# PWR.net
KiCad netlist of a schematic drawn in Altium Designer
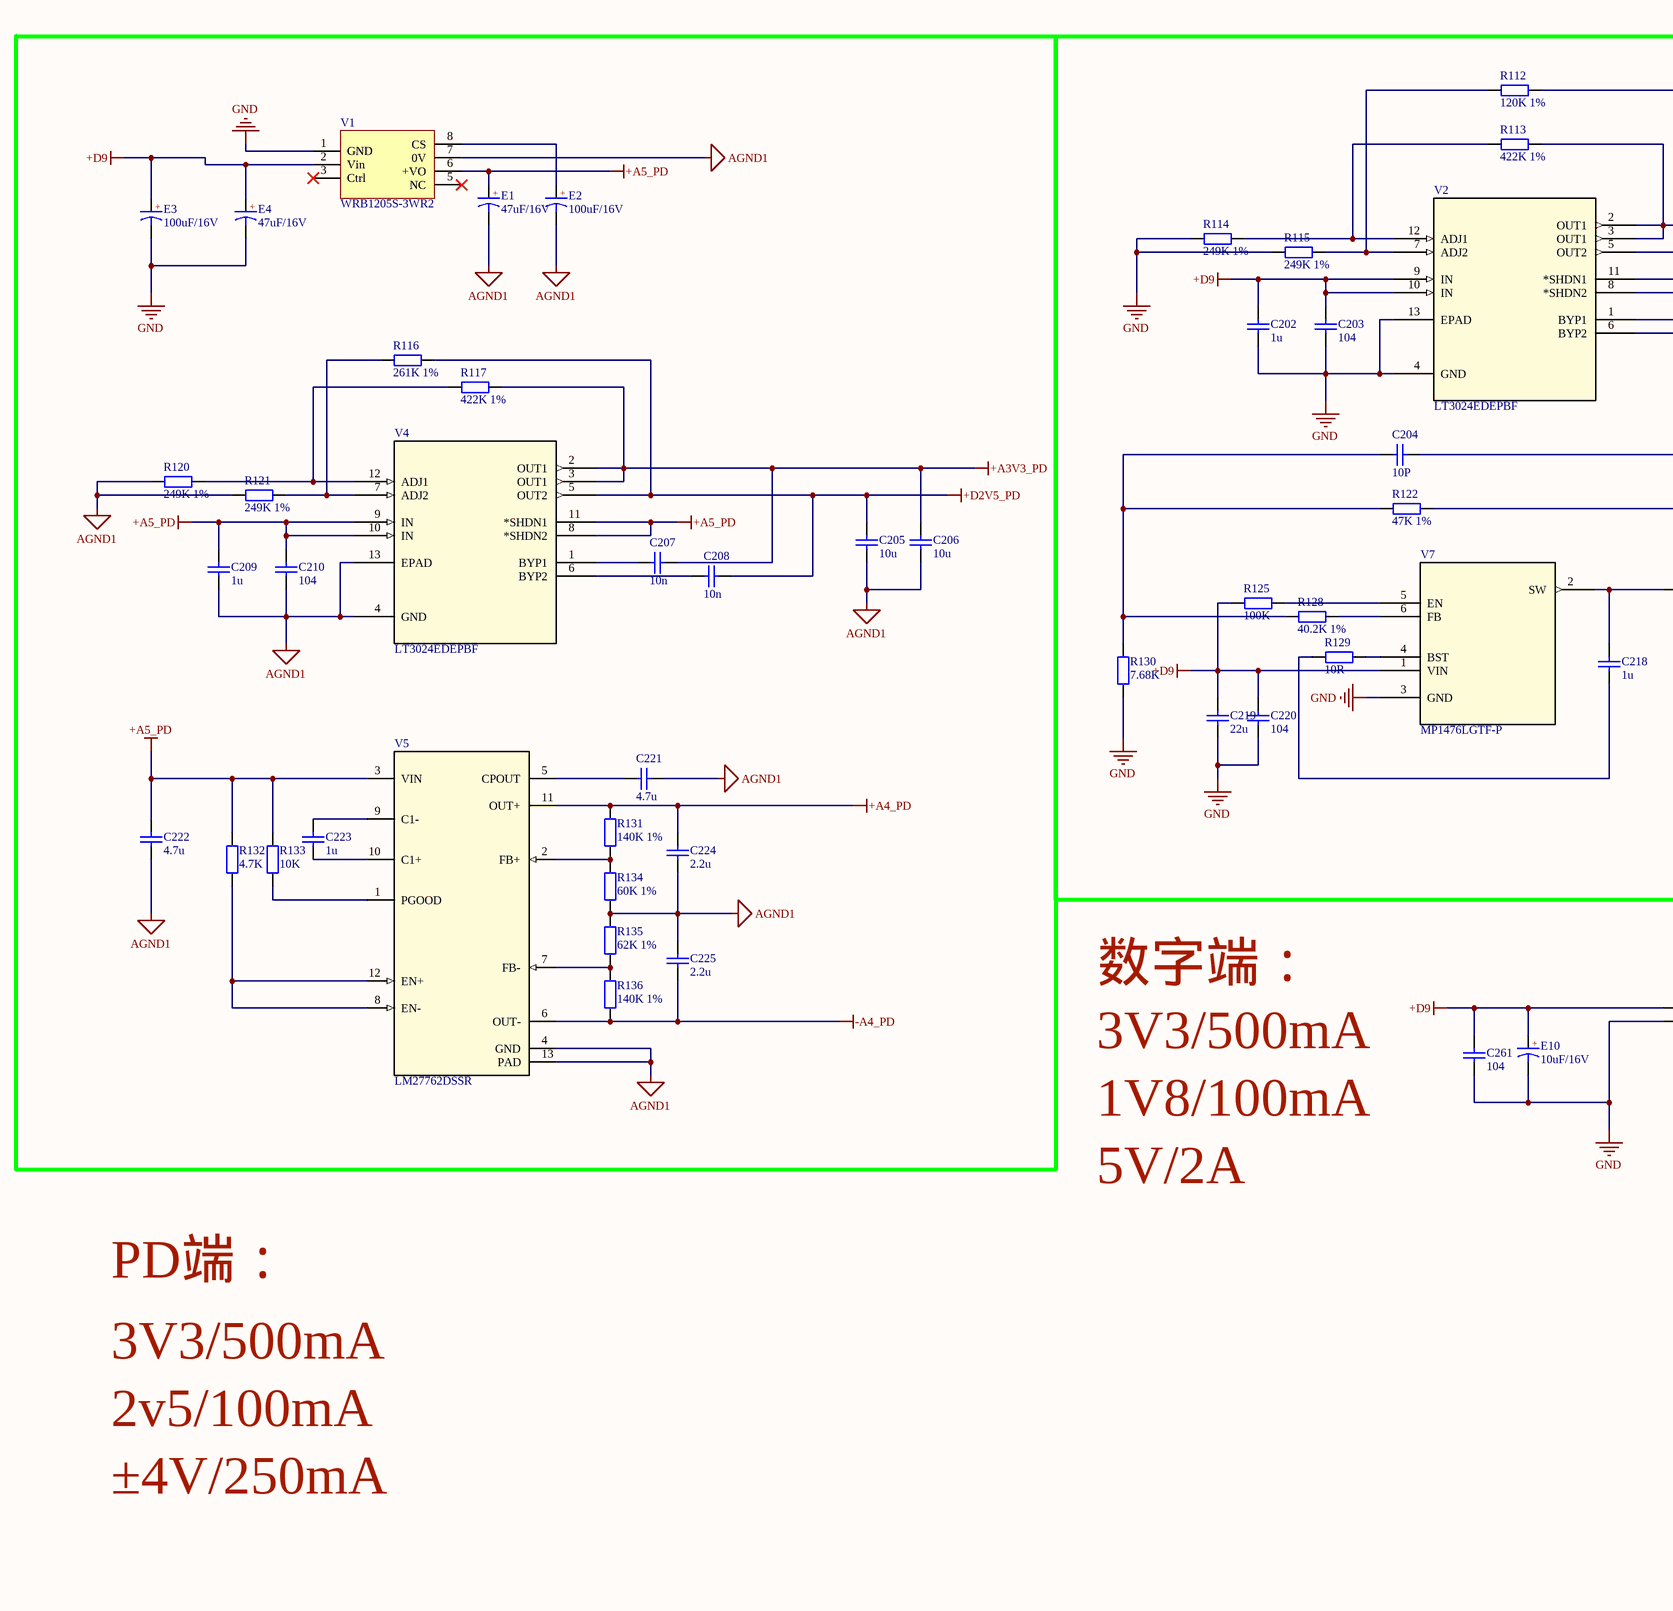
[diagram p0: PWR.SchDoc, left]
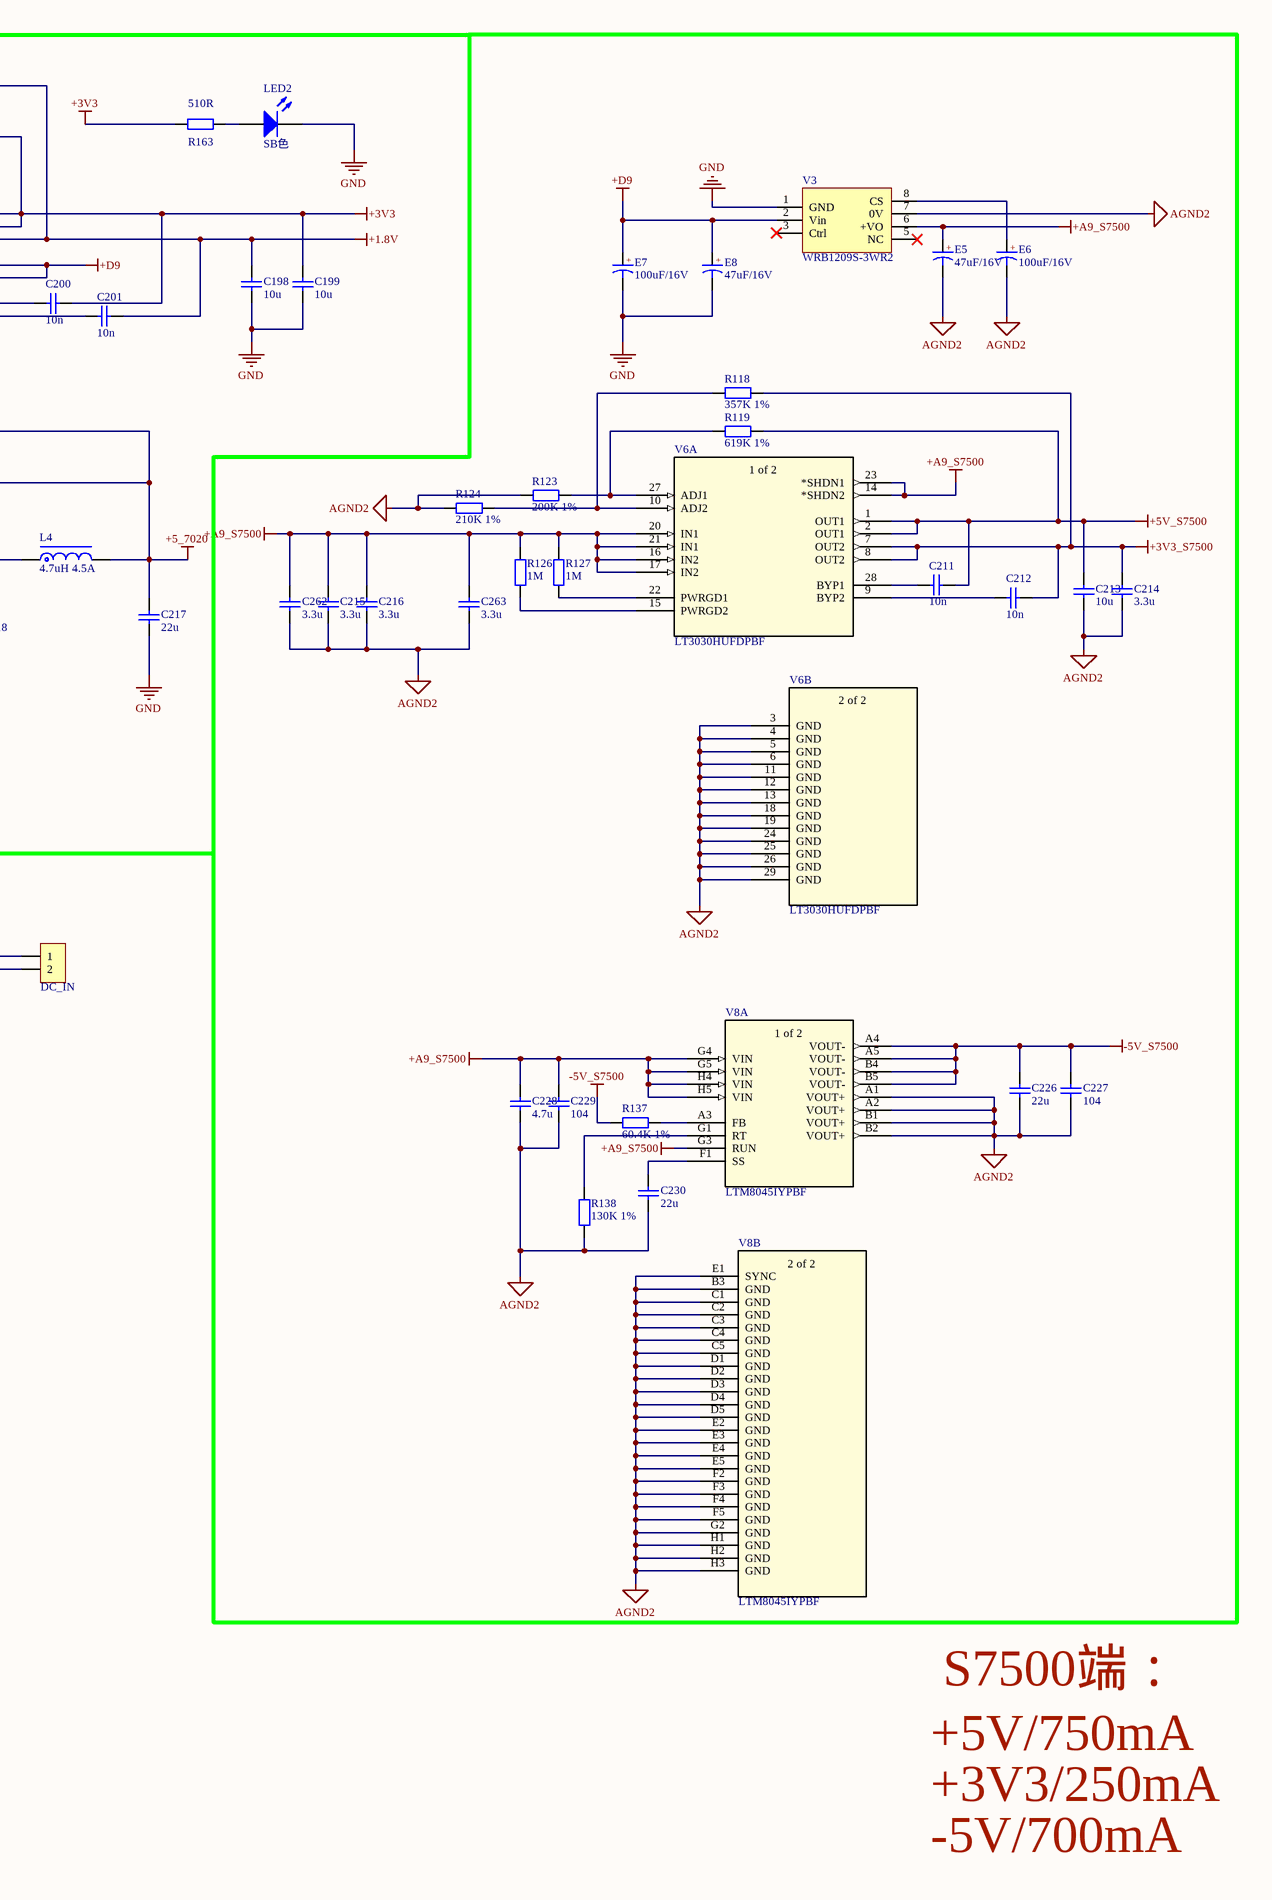
[diagram p1: PWR.SchDoc, right]

(export (version "E")
  (design (tool "Eeschema 10.0.6"))
  (components
    (comp (ref "C198")
      (value "10u")
      (footprint "C0402_L")
      (description "贴片电容/MLCC电容")
      (libsource (lib "0.1 - 电阻-电容-电感-保险丝-晶振-晶体-磁珠-电位器-法拉电容-馈通电容") (part "C"))
    )
    (comp (ref "C199")
      (value "10u")
      (footprint "C0402_L")
      (description "贴片电容/MLCC电容")
      (libsource (lib "0.1 - 电阻-电容-电感-保险丝-晶振-晶体-磁珠-电位器-法拉电容-馈通电容") (part "C"))
    )
    (comp (ref "C200")
      (value "10n")
      (footprint "C0402_L")
      (description "贴片电容/MLCC电容")
      (libsource (lib "0.1 - 电阻-电容-电感-保险丝-晶振-晶体-磁珠-电位器-法拉电容-馈通电容") (part "C"))
    )
    (comp (ref "C201")
      (value "10n")
      (footprint "C0402_L")
      (description "贴片电容/MLCC电容")
      (libsource (lib "0.1 - 电阻-电容-电感-保险丝-晶振-晶体-磁珠-电位器-法拉电容-馈通电容") (part "C"))
    )
    (comp (ref "C202")
      (value "1u")
      (footprint "C0402_L")
      (description "贴片电容/MLCC电容")
      (libsource (lib "0.1 - 电阻-电容-电感-保险丝-晶振-晶体-磁珠-电位器-法拉电容-馈通电容") (part "C"))
    )
    (comp (ref "C203")
      (value "104")
      (footprint "C0402_L")
      (description "贴片电容/MLCC电容")
      (libsource (lib "0.1 - 电阻-电容-电感-保险丝-晶振-晶体-磁珠-电位器-法拉电容-馈通电容") (part "C"))
    )
    (comp (ref "C204")
      (value "10P")
      (footprint "C0402_L")
      (description "贴片电容/MLCC电容")
      (libsource (lib "0.1 - 电阻-电容-电感-保险丝-晶振-晶体-磁珠-电位器-法拉电容-馈通电容") (part "C"))
    )
    (comp (ref "C205")
      (value "10u")
      (footprint "C0402_L")
      (description "贴片电容/MLCC电容")
      (libsource (lib "0.1 - 电阻-电容-电感-保险丝-晶振-晶体-磁珠-电位器-法拉电容-馈通电容") (part "C"))
    )
    (comp (ref "C206")
      (value "10u")
      (footprint "C0402_L")
      (description "贴片电容/MLCC电容")
      (libsource (lib "0.1 - 电阻-电容-电感-保险丝-晶振-晶体-磁珠-电位器-法拉电容-馈通电容") (part "C"))
    )
    (comp (ref "C207")
      (value "10n")
      (footprint "C0402_L")
      (description "贴片电容/MLCC电容")
      (libsource (lib "0.1 - 电阻-电容-电感-保险丝-晶振-晶体-磁珠-电位器-法拉电容-馈通电容") (part "C"))
    )
    (comp (ref "C208")
      (value "10n")
      (footprint "C0402_L")
      (description "贴片电容/MLCC电容")
      (libsource (lib "0.1 - 电阻-电容-电感-保险丝-晶振-晶体-磁珠-电位器-法拉电容-馈通电容") (part "C"))
    )
    (comp (ref "C209")
      (value "1u")
      (footprint "C0402_L")
      (description "贴片电容/MLCC电容")
      (libsource (lib "0.1 - 电阻-电容-电感-保险丝-晶振-晶体-磁珠-电位器-法拉电容-馈通电容") (part "C"))
    )
    (comp (ref "C210")
      (value "104")
      (footprint "C0402_L")
      (description "贴片电容/MLCC电容")
      (libsource (lib "0.1 - 电阻-电容-电感-保险丝-晶振-晶体-磁珠-电位器-法拉电容-馈通电容") (part "C"))
    )
    (comp (ref "C211")
      (value "10n")
      (footprint "C0402_L")
      (description "贴片电容/MLCC电容")
      (libsource (lib "0.1 - 电阻-电容-电感-保险丝-晶振-晶体-磁珠-电位器-法拉电容-馈通电容") (part "C"))
    )
    (comp (ref "C212")
      (value "10n")
      (footprint "C0402_L")
      (description "贴片电容/MLCC电容")
      (libsource (lib "0.1 - 电阻-电容-电感-保险丝-晶振-晶体-磁珠-电位器-法拉电容-馈通电容") (part "C"))
    )
    (comp (ref "C213")
      (value "10u")
      (footprint "C0402_L")
      (description "贴片电容/MLCC电容")
      (libsource (lib "0.1 - 电阻-电容-电感-保险丝-晶振-晶体-磁珠-电位器-法拉电容-馈通电容") (part "C"))
    )
    (comp (ref "C214")
      (value "3.3u")
      (footprint "C0402_L")
      (description "贴片电容/MLCC电容")
      (libsource (lib "0.1 - 电阻-电容-电感-保险丝-晶振-晶体-磁珠-电位器-法拉电容-馈通电容") (part "C"))
    )
    (comp (ref "C215")
      (value "3.3u")
      (footprint "C0402_L")
      (description "贴片电容/MLCC电容")
      (libsource (lib "0.1 - 电阻-电容-电感-保险丝-晶振-晶体-磁珠-电位器-法拉电容-馈通电容") (part "C"))
    )
    (comp (ref "C216")
      (value "3.3u")
      (footprint "C0402_L")
      (description "贴片电容/MLCC电容")
      (libsource (lib "0.1 - 电阻-电容-电感-保险丝-晶振-晶体-磁珠-电位器-法拉电容-馈通电容") (part "C"))
    )
    (comp (ref "C217")
      (value "22u")
      (footprint "C0402_L")
      (description "贴片电容/MLCC电容")
      (libsource (lib "0.1 - 电阻-电容-电感-保险丝-晶振-晶体-磁珠-电位器-法拉电容-馈通电容") (part "C"))
    )
    (comp (ref "C218")
      (value "1u")
      (footprint "C0402_L")
      (description "贴片电容/MLCC电容")
      (libsource (lib "0.1 - 电阻-电容-电感-保险丝-晶振-晶体-磁珠-电位器-法拉电容-馈通电容") (part "C"))
    )
    (comp (ref "C219")
      (value "22u")
      (footprint "C0402_L")
      (description "贴片电容/MLCC电容")
      (libsource (lib "0.1 - 电阻-电容-电感-保险丝-晶振-晶体-磁珠-电位器-法拉电容-馈通电容") (part "C"))
    )
    (comp (ref "C220")
      (value "104")
      (footprint "C0402_L")
      (description "贴片电容/MLCC电容")
      (libsource (lib "0.1 - 电阻-电容-电感-保险丝-晶振-晶体-磁珠-电位器-法拉电容-馈通电容") (part "C"))
    )
    (comp (ref "C221")
      (value "4.7u")
      (footprint "C0402_L")
      (description "贴片电容/MLCC电容")
      (libsource (lib "0.1 - 电阻-电容-电感-保险丝-晶振-晶体-磁珠-电位器-法拉电容-馈通电容") (part "C"))
    )
    (comp (ref "C222")
      (value "4.7u")
      (footprint "C0402_L")
      (description "贴片电容/MLCC电容")
      (libsource (lib "0.1 - 电阻-电容-电感-保险丝-晶振-晶体-磁珠-电位器-法拉电容-馈通电容") (part "C"))
    )
    (comp (ref "C223")
      (value "1u")
      (footprint "C0402_L")
      (description "贴片电容/MLCC电容")
      (libsource (lib "0.1 - 电阻-电容-电感-保险丝-晶振-晶体-磁珠-电位器-法拉电容-馈通电容") (part "C"))
    )
    (comp (ref "C224")
      (value "2.2u")
      (footprint "C0402_L")
      (description "贴片电容/MLCC电容")
      (libsource (lib "0.1 - 电阻-电容-电感-保险丝-晶振-晶体-磁珠-电位器-法拉电容-馈通电容") (part "C"))
    )
    (comp (ref "C225")
      (value "2.2u")
      (footprint "C0402_L")
      (description "贴片电容/MLCC电容")
      (libsource (lib "0.1 - 电阻-电容-电感-保险丝-晶振-晶体-磁珠-电位器-法拉电容-馈通电容") (part "C"))
    )
    (comp (ref "C226")
      (value "22u")
      (footprint "C0402_L")
      (description "贴片电容/MLCC电容")
      (libsource (lib "0.1 - 电阻-电容-电感-保险丝-晶振-晶体-磁珠-电位器-法拉电容-馈通电容") (part "C"))
    )
    (comp (ref "C227")
      (value "104")
      (footprint "C0402_L")
      (description "贴片电容/MLCC电容")
      (libsource (lib "0.1 - 电阻-电容-电感-保险丝-晶振-晶体-磁珠-电位器-法拉电容-馈通电容") (part "C"))
    )
    (comp (ref "C228")
      (value "4.7u")
      (footprint "C0402_L")
      (description "贴片电容/MLCC电容")
      (libsource (lib "0.1 - 电阻-电容-电感-保险丝-晶振-晶体-磁珠-电位器-法拉电容-馈通电容") (part "C"))
    )
    (comp (ref "C229")
      (value "104")
      (footprint "C0402_L")
      (description "贴片电容/MLCC电容")
      (libsource (lib "0.1 - 电阻-电容-电感-保险丝-晶振-晶体-磁珠-电位器-法拉电容-馈通电容") (part "C"))
    )
    (comp (ref "C230")
      (value "22u")
      (footprint "C0402_L")
      (description "贴片电容/MLCC电容")
      (libsource (lib "0.1 - 电阻-电容-电感-保险丝-晶振-晶体-磁珠-电位器-法拉电容-馈通电容") (part "C"))
    )
    (comp (ref "C261")
      (value "104")
      (footprint "C0402_L")
      (description "贴片电容/MLCC电容")
      (libsource (lib "0.1 - 电阻-电容-电感-保险丝-晶振-晶体-磁珠-电位器-法拉电容-馈通电容") (part "C"))
    )
    (comp (ref "C262")
      (value "3.3u")
      (footprint "C0402_L")
      (description "贴片电容/MLCC电容")
      (libsource (lib "0.1 - 电阻-电容-电感-保险丝-晶振-晶体-磁珠-电位器-法拉电容-馈通电容") (part "C"))
    )
    (comp (ref "C263")
      (value "3.3u")
      (footprint "C0402_L")
      (description "贴片电容/MLCC电容")
      (libsource (lib "0.1 - 电阻-电容-电感-保险丝-晶振-晶体-磁珠-电位器-法拉电容-馈通电容") (part "C"))
    )
    (comp (ref "DC_IN")
      (value "HDR-1X2")
      (footprint "KF128-3.81-2P")
      (description "2P接插件")
      (libsource (lib "5.7 - 3.81mm连接器(KF128-KF2EDGVHM)") (part "Header 2"))
    )
    (comp (ref "E1")
      (value "47uF/16V")
      (footprint "C_6032")
      (description "贴片钽电容")
      (libsource (lib "0.1 - 电阻-电容-电感-保险丝-晶振-晶体-磁珠-电位器-法拉电容-馈通电容") (part "CT"))
    )
    (comp (ref "E2")
      (value "100uF/16V")
      (footprint "C_6032")
      (description "贴片钽电容")
      (libsource (lib "0.1 - 电阻-电容-电感-保险丝-晶振-晶体-磁珠-电位器-法拉电容-馈通电容") (part "CT"))
    )
    (comp (ref "E3")
      (value "100uF/16V")
      (footprint "C_6032")
      (description "贴片钽电容")
      (libsource (lib "0.1 - 电阻-电容-电感-保险丝-晶振-晶体-磁珠-电位器-法拉电容-馈通电容") (part "CT"))
    )
    (comp (ref "E4")
      (value "47uF/16V")
      (footprint "C_6032")
      (description "贴片钽电容")
      (libsource (lib "0.1 - 电阻-电容-电感-保险丝-晶振-晶体-磁珠-电位器-法拉电容-馈通电容") (part "CT"))
    )
    (comp (ref "E5")
      (value "47uF/16V")
      (footprint "C_6032")
      (description "贴片钽电容")
      (libsource (lib "0.1 - 电阻-电容-电感-保险丝-晶振-晶体-磁珠-电位器-法拉电容-馈通电容") (part "CT"))
    )
    (comp (ref "E6")
      (value "100uF/16V")
      (footprint "C_6032")
      (description "贴片钽电容")
      (libsource (lib "0.1 - 电阻-电容-电感-保险丝-晶振-晶体-磁珠-电位器-法拉电容-馈通电容") (part "CT"))
    )
    (comp (ref "E7")
      (value "100uF/16V")
      (footprint "C_6032")
      (description "贴片钽电容")
      (libsource (lib "0.1 - 电阻-电容-电感-保险丝-晶振-晶体-磁珠-电位器-法拉电容-馈通电容") (part "CT"))
    )
    (comp (ref "E8")
      (value "47uF/16V")
      (footprint "C_6032")
      (description "贴片钽电容")
      (libsource (lib "0.1 - 电阻-电容-电感-保险丝-晶振-晶体-磁珠-电位器-法拉电容-馈通电容") (part "CT"))
    )
    (comp (ref "E10")
      (value "10uF/16V")
      (footprint "C_3216")
      (description "贴片钽电容")
      (libsource (lib "0.1 - 电阻-电容-电感-保险丝-晶振-晶体-磁珠-电位器-法拉电容-馈通电容") (part "CT"))
    )
    (comp (ref "L4")
      (value "4.7uH 4.5A")
      (footprint "SWPA5020")
      (description "顺络_SWPA贴片屏蔽电感")
      (libsource (lib "0.1 - 电阻-电容-电感-保险丝-晶振-晶体-磁珠-电位器-法拉电容-馈通电容") (part "L-SWPA"))
    )
    (comp (ref "LED2")
      (value "SB色")
      (footprint "LED0603_B")
      (description "贴片LED")
      (libsource (lib "0.3 - LED发光二极管-IR二极管_接收管-光耦") (part "LED"))
    )
    (comp (ref "R112")
      (value "120K 1%")
      (footprint "R0402_L")
      (description "贴片电阻")
      (libsource (lib "0.1 - 电阻-电容-电感-保险丝-晶振-晶体-磁珠-电位器-法拉电容-馈通电容") (part "R"))
    )
    (comp (ref "R113")
      (value "422K 1%")
      (footprint "R0402_L")
      (description "贴片电阻")
      (libsource (lib "0.1 - 电阻-电容-电感-保险丝-晶振-晶体-磁珠-电位器-法拉电容-馈通电容") (part "R"))
    )
    (comp (ref "R114")
      (value "249K 1%")
      (footprint "R0402_L")
      (description "贴片电阻")
      (libsource (lib "0.1 - 电阻-电容-电感-保险丝-晶振-晶体-磁珠-电位器-法拉电容-馈通电容") (part "R"))
    )
    (comp (ref "R115")
      (value "249K 1%")
      (footprint "R0402_L")
      (description "贴片电阻")
      (libsource (lib "0.1 - 电阻-电容-电感-保险丝-晶振-晶体-磁珠-电位器-法拉电容-馈通电容") (part "R"))
    )
    (comp (ref "R116")
      (value "261K 1%")
      (footprint "R0402_L")
      (description "贴片电阻")
      (libsource (lib "0.1 - 电阻-电容-电感-保险丝-晶振-晶体-磁珠-电位器-法拉电容-馈通电容") (part "R"))
    )
    (comp (ref "R117")
      (value "422K 1%")
      (footprint "R0402_L")
      (description "贴片电阻")
      (libsource (lib "0.1 - 电阻-电容-电感-保险丝-晶振-晶体-磁珠-电位器-法拉电容-馈通电容") (part "R"))
    )
    (comp (ref "R118")
      (value "357K 1%")
      (footprint "R0402_L")
      (description "贴片电阻")
      (libsource (lib "0.1 - 电阻-电容-电感-保险丝-晶振-晶体-磁珠-电位器-法拉电容-馈通电容") (part "R"))
    )
    (comp (ref "R119")
      (value "619K 1%")
      (footprint "R0402_L")
      (description "贴片电阻")
      (libsource (lib "0.1 - 电阻-电容-电感-保险丝-晶振-晶体-磁珠-电位器-法拉电容-馈通电容") (part "R"))
    )
    (comp (ref "R120")
      (value "249K 1%")
      (footprint "R0402_L")
      (description "贴片电阻")
      (libsource (lib "0.1 - 电阻-电容-电感-保险丝-晶振-晶体-磁珠-电位器-法拉电容-馈通电容") (part "R"))
    )
    (comp (ref "R121")
      (value "249K 1%")
      (footprint "R0402_L")
      (description "贴片电阻")
      (libsource (lib "0.1 - 电阻-电容-电感-保险丝-晶振-晶体-磁珠-电位器-法拉电容-馈通电容") (part "R"))
    )
    (comp (ref "R122")
      (value "47K 1%")
      (footprint "R0402_L")
      (description "贴片电阻")
      (libsource (lib "0.1 - 电阻-电容-电感-保险丝-晶振-晶体-磁珠-电位器-法拉电容-馈通电容") (part "R"))
    )
    (comp (ref "R123")
      (value "200K 1%")
      (footprint "R0402_L")
      (description "贴片电阻")
      (libsource (lib "0.1 - 电阻-电容-电感-保险丝-晶振-晶体-磁珠-电位器-法拉电容-馈通电容") (part "R"))
    )
    (comp (ref "R124")
      (value "210K 1%")
      (footprint "R0402_L")
      (description "贴片电阻")
      (libsource (lib "0.1 - 电阻-电容-电感-保险丝-晶振-晶体-磁珠-电位器-法拉电容-馈通电容") (part "R"))
    )
    (comp (ref "R125")
      (value "100K")
      (footprint "R0402_L")
      (description "贴片电阻")
      (libsource (lib "0.1 - 电阻-电容-电感-保险丝-晶振-晶体-磁珠-电位器-法拉电容-馈通电容") (part "R"))
    )
    (comp (ref "R126")
      (value "1M")
      (footprint "R0402_L")
      (description "贴片电阻")
      (libsource (lib "0.1 - 电阻-电容-电感-保险丝-晶振-晶体-磁珠-电位器-法拉电容-馈通电容") (part "R"))
    )
    (comp (ref "R127")
      (value "1M")
      (footprint "R0402_L")
      (description "贴片电阻")
      (libsource (lib "0.1 - 电阻-电容-电感-保险丝-晶振-晶体-磁珠-电位器-法拉电容-馈通电容") (part "R"))
    )
    (comp (ref "R128")
      (value "40.2K 1%")
      (footprint "R0402_L")
      (description "贴片电阻")
      (libsource (lib "0.1 - 电阻-电容-电感-保险丝-晶振-晶体-磁珠-电位器-法拉电容-馈通电容") (part "R"))
    )
    (comp (ref "R129")
      (value "10R")
      (footprint "R0402_L")
      (description "贴片电阻")
      (libsource (lib "0.1 - 电阻-电容-电感-保险丝-晶振-晶体-磁珠-电位器-法拉电容-馈通电容") (part "R"))
    )
    (comp (ref "R130")
      (value "7.68K")
      (footprint "R0402_L")
      (description "贴片电阻")
      (libsource (lib "0.1 - 电阻-电容-电感-保险丝-晶振-晶体-磁珠-电位器-法拉电容-馈通电容") (part "R"))
    )
    (comp (ref "R131")
      (value "140K 1%")
      (footprint "R0402_L")
      (description "贴片电阻")
      (libsource (lib "0.1 - 电阻-电容-电感-保险丝-晶振-晶体-磁珠-电位器-法拉电容-馈通电容") (part "R"))
    )
    (comp (ref "R132")
      (value "4.7K")
      (footprint "R0402_L")
      (description "贴片电阻")
      (libsource (lib "0.1 - 电阻-电容-电感-保险丝-晶振-晶体-磁珠-电位器-法拉电容-馈通电容") (part "R"))
    )
    (comp (ref "R133")
      (value "10K")
      (footprint "R0402_L")
      (description "贴片电阻")
      (libsource (lib "0.1 - 电阻-电容-电感-保险丝-晶振-晶体-磁珠-电位器-法拉电容-馈通电容") (part "R"))
    )
    (comp (ref "R134")
      (value "60K 1%")
      (footprint "R0402_L")
      (description "贴片电阻")
      (libsource (lib "0.1 - 电阻-电容-电感-保险丝-晶振-晶体-磁珠-电位器-法拉电容-馈通电容") (part "R"))
    )
    (comp (ref "R135")
      (value "62K 1%")
      (footprint "R0402_L")
      (description "贴片电阻")
      (libsource (lib "0.1 - 电阻-电容-电感-保险丝-晶振-晶体-磁珠-电位器-法拉电容-馈通电容") (part "R"))
    )
    (comp (ref "R136")
      (value "140K 1%")
      (footprint "R0402_L")
      (description "贴片电阻")
      (libsource (lib "0.1 - 电阻-电容-电感-保险丝-晶振-晶体-磁珠-电位器-法拉电容-馈通电容") (part "R"))
    )
    (comp (ref "R137")
      (value "60.4K 1%")
      (footprint "R0402_L")
      (description "贴片电阻")
      (libsource (lib "0.1 - 电阻-电容-电感-保险丝-晶振-晶体-磁珠-电位器-法拉电容-馈通电容") (part "R"))
    )
    (comp (ref "R138")
      (value "130K 1%")
      (footprint "R0402_L")
      (description "贴片电阻")
      (libsource (lib "0.1 - 电阻-电容-电感-保险丝-晶振-晶体-磁珠-电位器-法拉电容-馈通电容") (part "R"))
    )
    (comp (ref "R163")
      (value "510R")
      (footprint "R0603_L")
      (description "贴片电阻")
      (libsource (lib "0.1 - 电阻-电容-电感-保险丝-晶振-晶体-磁珠-电位器-法拉电容-馈通电容") (part "R"))
    )
    (comp (ref "V1")
      (value "WRB1205S-3WR2")
      (footprint "WRB_S-3WR2")
      (libsource (lib "WRB_S-3WR2") (part "WRB_S-3WR2"))
    )
    (comp (ref "V2")
      (value "LT3024EDEPBF")
      (footprint "DFN-12_DE_LIT")
      (description "No Description Available")
      (libsource (lib "LT3024EDEPBF") (part "LT3024EDEPBF"))
    )
    (comp (ref "V3")
      (value "WRB1209S-3WR2")
      (footprint "WRB_S-3WR2")
      (libsource (lib "WRB_S-3WR2") (part "WRB_S-3WR2"))
    )
    (comp (ref "V4")
      (value "LT3024EDEPBF")
      (footprint "DFN-12_DE_LIT")
      (description "No Description Available")
      (libsource (lib "LT3024EDEPBF") (part "LT3024EDEPBF"))
    )
    (comp (ref "V5")
      (value "LM27762DSSR")
      (footprint "DSS0012B")
      (description "No Description Available")
      (fields (field (name "COPYRIGHT") "Copyright (C) 2023 Ultra Librarian. All rights reserved."))
      (libsource (lib "LM27762DSSR") (part "LM27762DSSR"))
    )
    (comp (ref "V6")
      (value "LT3030HUFDPBF")
      (footprint "QFN-28_UFD_LIT")
      (description "No Description Available")
      (libsource (lib "LT3030HUFDPBF") (part "LT3030HUFDPBF"))
    )
    (comp (ref "V7")
      (value "MP1476LGTF-P")
      (footprint "SOT563_MP1476L_MNP")
      (description "No Description Available")
      (libsource (lib "MP1476LGTF-P") (part "MP1476LGTF-P"))
    )
    (comp (ref "V8")
      (value "LTM8045IYPBF")
      (footprint "BGA-40_11P25X6P25_LIT")
      (description "No Description Available")
      (libsource (lib "LTM8045IYPBF") (part "LTM8045IYPBF"))
    )
  )
  (nets
    (net (code "1") (name "+1.8V") (class "Default")
      (node (ref "C198") (pin "1") (pinfunction "1_1") (pintype "passive"))
      (node (ref "C201") (pin "2") (pinfunction "2_2") (pintype "passive"))
      (node (ref "R112") (pin "2") (pinfunction "2_2") (pintype "passive"))
      (node (ref "V2") (pin "5") (pinfunction "OUT2_5") (pintype "output"))
    )
    (net (code "2") (name "+3V3") (class "Default")
      (node (ref "C199") (pin "1") (pinfunction "1_1") (pintype "passive"))
      (node (ref "C200") (pin "2") (pinfunction "2_2") (pintype "passive"))
      (node (ref "R113") (pin "2") (pinfunction "2_2") (pintype "passive"))
      (node (ref "R163") (pin "1") (pinfunction "1_1") (pintype "passive"))
      (node (ref "V2") (pin "2") (pinfunction "OUT1_2") (pintype "output"))
      (node (ref "V2") (pin "3") (pinfunction "OUT1_3") (pintype "output"))
    )
    (net (code "3") (name "+3V3_S7500") (class "Default")
      (node (ref "C212") (pin "2") (pinfunction "2_2") (pintype "passive"))
      (node (ref "C214") (pin "2") (pinfunction "2_2") (pintype "passive"))
      (node (ref "R118") (pin "2") (pinfunction "2_2") (pintype "passive"))
      (node (ref "V6") (pin "7") (pinfunction "OUT2_7") (pintype "output"))
      (node (ref "V6") (pin "8") (pinfunction "OUT2_8") (pintype "output"))
    )
    (net (code "4") (name "+5V_S7500") (class "Default")
      (node (ref "C211") (pin "2") (pinfunction "2_2") (pintype "passive"))
      (node (ref "C213") (pin "2") (pinfunction "2_2") (pintype "passive"))
      (node (ref "R119") (pin "2") (pinfunction "2_2") (pintype "passive"))
      (node (ref "V6") (pin "1") (pinfunction "OUT1_1") (pintype "output"))
      (node (ref "V6") (pin "2") (pinfunction "OUT1_2") (pintype "output"))
    )
    (net (code "5") (name "+5_7020") (class "Default")
      (node (ref "C204") (pin "2") (pinfunction "2_2") (pintype "passive"))
      (node (ref "C217") (pin "2") (pinfunction "2_2") (pintype "passive"))
      (node (ref "L4") (pin "2") (pinfunction "2_2") (pintype "passive"))
      (node (ref "R122") (pin "2") (pinfunction "2_2") (pintype "passive"))
    )
    (net (code "6") (name "+A3V3_PD") (class "Default")
      (node (ref "C206") (pin "1") (pinfunction "1_1") (pintype "passive"))
      (node (ref "C207") (pin "2") (pinfunction "2_2") (pintype "passive"))
      (node (ref "R117") (pin "2") (pinfunction "2_2") (pintype "passive"))
      (node (ref "V4") (pin "2") (pinfunction "OUT1_2") (pintype "output"))
      (node (ref "V4") (pin "3") (pinfunction "OUT1_3") (pintype "output"))
    )
    (net (code "7") (name "+A4_PD") (class "Default")
      (node (ref "C224") (pin "2") (pinfunction "2_2") (pintype "passive"))
      (node (ref "R131") (pin "2") (pinfunction "2_2") (pintype "passive"))
      (node (ref "V5") (pin "11") (pinfunction "OUT+_11") (pintype "power_in"))
    )
    (net (code "8") (name "+A5_PD") (class "Default")
      (node (ref "C209") (pin "1") (pinfunction "1_1") (pintype "passive"))
      (node (ref "C210") (pin "1") (pinfunction "1_1") (pintype "passive"))
      (node (ref "C222") (pin "1") (pinfunction "1_1") (pintype "passive"))
      (node (ref "E1") (pin "1") (pinfunction "A_1") (pintype "passive"))
      (node (ref "R132") (pin "2") (pinfunction "2_2") (pintype "passive"))
      (node (ref "R133") (pin "2") (pinfunction "2_2") (pintype "passive"))
      (node (ref "V1") (pin "6") (pinfunction "+VO_6") (pintype "passive"))
      (node (ref "V4") (pin "10") (pinfunction "IN_10") (pintype "input"))
      (node (ref "V4") (pin "11") (pinfunction "*SHDN1_11") (pintype "passive"))
      (node (ref "V4") (pin "8") (pinfunction "*SHDN2_8") (pintype "passive"))
      (node (ref "V4") (pin "9") (pinfunction "IN_9") (pintype "input"))
      (node (ref "V5") (pin "3") (pinfunction "VIN_3") (pintype "power_in"))
    )
    (net (code "9") (name "+A9_S7500") (class "Default")
      (node (ref "C215") (pin "2") (pinfunction "2_2") (pintype "passive"))
      (node (ref "C216") (pin "2") (pinfunction "2_2") (pintype "passive"))
      (node (ref "C228") (pin "1") (pinfunction "1_1") (pintype "passive"))
      (node (ref "C229") (pin "1") (pinfunction "1_1") (pintype "passive"))
      (node (ref "C262") (pin "2") (pinfunction "2_2") (pintype "passive"))
      (node (ref "C263") (pin "2") (pinfunction "2_2") (pintype "passive"))
      (node (ref "E5") (pin "1") (pinfunction "A_1") (pintype "passive"))
      (node (ref "R126") (pin "2") (pinfunction "2_2") (pintype "passive"))
      (node (ref "R127") (pin "2") (pinfunction "2_2") (pintype "passive"))
      (node (ref "V3") (pin "6") (pinfunction "+VO_6") (pintype "passive"))
      (node (ref "V6") (pin "14") (pinfunction "*SHDN2_14") (pintype "output"))
      (node (ref "V6") (pin "16") (pinfunction "IN2_16") (pintype "input"))
      (node (ref "V6") (pin "17") (pinfunction "IN2_17") (pintype "input"))
      (node (ref "V6") (pin "20") (pinfunction "IN1_20") (pintype "input"))
      (node (ref "V6") (pin "21") (pinfunction "IN1_21") (pintype "input"))
      (node (ref "V6") (pin "23") (pinfunction "*SHDN1_23") (pintype "output"))
      (node (ref "V8") (pin "G3") (pinfunction "RUN_G3") (pintype "passive"))
      (node (ref "V8") (pin "G4") (pinfunction "VIN_G4") (pintype "input"))
      (node (ref "V8") (pin "G5") (pinfunction "VIN_G5") (pintype "input"))
      (node (ref "V8") (pin "H4") (pinfunction "VIN_H4") (pintype "input"))
      (node (ref "V8") (pin "H5") (pinfunction "VIN_H5") (pintype "input"))
    )
    (net (code "10") (name "+D2V5_PD") (class "Default")
      (node (ref "C205") (pin "1") (pinfunction "1_1") (pintype "passive"))
      (node (ref "C208") (pin "2") (pinfunction "2_2") (pintype "passive"))
      (node (ref "R116") (pin "2") (pinfunction "2_2") (pintype "passive"))
      (node (ref "V4") (pin "5") (pinfunction "OUT2_5") (pintype "output"))
    )
    (net (code "11") (name "+D9") (class "Default")
      (node (ref "C202") (pin "1") (pinfunction "1_1") (pintype "passive"))
      (node (ref "C203") (pin "1") (pinfunction "1_1") (pintype "passive"))
      (node (ref "C219") (pin "2") (pinfunction "2_2") (pintype "passive"))
      (node (ref "C220") (pin "2") (pinfunction "2_2") (pintype "passive"))
      (node (ref "C261") (pin "2") (pinfunction "2_2") (pintype "passive"))
      (node (ref "DC_IN") (pin "1") (pinfunction "1_1") (pintype "passive"))
      (node (ref "E10") (pin "1") (pinfunction "A_1") (pintype "passive"))
      (node (ref "E3") (pin "1") (pinfunction "A_1") (pintype "passive"))
      (node (ref "E4") (pin "1") (pinfunction "A_1") (pintype "passive"))
      (node (ref "E7") (pin "1") (pinfunction "A_1") (pintype "passive"))
      (node (ref "E8") (pin "1") (pinfunction "A_1") (pintype "passive"))
      (node (ref "R125") (pin "1") (pinfunction "1_1") (pintype "passive"))
      (node (ref "V1") (pin "2") (pinfunction "Vin_2") (pintype "passive"))
      (node (ref "V2") (pin "10") (pinfunction "IN_10") (pintype "input"))
      (node (ref "V2") (pin "11") (pinfunction "*SHDN1_11") (pintype "passive"))
      (node (ref "V2") (pin "8") (pinfunction "*SHDN2_8") (pintype "passive"))
      (node (ref "V2") (pin "9") (pinfunction "IN_9") (pintype "input"))
      (node (ref "V3") (pin "2") (pinfunction "Vin_2") (pintype "passive"))
      (node (ref "V7") (pin "1") (pinfunction "VIN_1") (pintype "power_in"))
    )
    (net (code "12") (name "-5V_S7500") (class "Default")
      (node (ref "C226") (pin "1") (pinfunction "1_1") (pintype "passive"))
      (node (ref "C227") (pin "1") (pinfunction "1_1") (pintype "passive"))
      (node (ref "R137") (pin "1") (pinfunction "1_1") (pintype "passive"))
      (node (ref "V8") (pin "A4") (pinfunction "VOUT-_A4") (pintype "output"))
      (node (ref "V8") (pin "A5") (pinfunction "VOUT-_A5") (pintype "output"))
      (node (ref "V8") (pin "B4") (pinfunction "VOUT-_B4") (pintype "output"))
      (node (ref "V8") (pin "B5") (pinfunction "VOUT-_B5") (pintype "output"))
    )
    (net (code "13") (name "-A4_PD") (class "Default")
      (node (ref "C225") (pin "1") (pinfunction "1_1") (pintype "passive"))
      (node (ref "R136") (pin "1") (pinfunction "1_1") (pintype "passive"))
      (node (ref "V5") (pin "6") (pinfunction "OUT-_6") (pintype "power_in"))
    )
    (net (code "14") (name "AGND1") (class "Default")
      (node (ref "C205") (pin "2") (pinfunction "2_2") (pintype "passive"))
      (node (ref "C206") (pin "2") (pinfunction "2_2") (pintype "passive"))
      (node (ref "C209") (pin "2") (pinfunction "2_2") (pintype "passive"))
      (node (ref "C210") (pin "2") (pinfunction "2_2") (pintype "passive"))
      (node (ref "C221") (pin "2") (pinfunction "2_2") (pintype "passive"))
      (node (ref "C222") (pin "2") (pinfunction "2_2") (pintype "passive"))
      (node (ref "C224") (pin "1") (pinfunction "1_1") (pintype "passive"))
      (node (ref "C225") (pin "2") (pinfunction "2_2") (pintype "passive"))
      (node (ref "E1") (pin "2") (pinfunction "K_2") (pintype "passive"))
      (node (ref "E2") (pin "2") (pinfunction "K_2") (pintype "passive"))
      (node (ref "R120") (pin "1") (pinfunction "1_1") (pintype "passive"))
      (node (ref "R121") (pin "1") (pinfunction "1_1") (pintype "passive"))
      (node (ref "R134") (pin "1") (pinfunction "1_1") (pintype "passive"))
      (node (ref "R135") (pin "2") (pinfunction "2_2") (pintype "passive"))
      (node (ref "V1") (pin "7") (pinfunction "0V_7") (pintype "passive"))
      (node (ref "V4") (pin "13") (pinfunction "EPAD_13") (pintype "passive"))
      (node (ref "V4") (pin "4") (pinfunction "GND_4") (pintype "power_in"))
      (node (ref "V5") (pin "13") (pinfunction "PAD_13") (pintype "power_in"))
      (node (ref "V5") (pin "4") (pinfunction "GND_4") (pintype "power_in"))
    )
    (net (code "15") (name "AGND2") (class "Default")
      (node (ref "C213") (pin "1") (pinfunction "1_1") (pintype "passive"))
      (node (ref "C214") (pin "1") (pinfunction "1_1") (pintype "passive"))
      (node (ref "C215") (pin "1") (pinfunction "1_1") (pintype "passive"))
      (node (ref "C216") (pin "1") (pinfunction "1_1") (pintype "passive"))
      (node (ref "C226") (pin "2") (pinfunction "2_2") (pintype "passive"))
      (node (ref "C227") (pin "2") (pinfunction "2_2") (pintype "passive"))
      (node (ref "C228") (pin "2") (pinfunction "2_2") (pintype "passive"))
      (node (ref "C229") (pin "2") (pinfunction "2_2") (pintype "passive"))
      (node (ref "C230") (pin "2") (pinfunction "2_2") (pintype "passive"))
      (node (ref "C262") (pin "1") (pinfunction "1_1") (pintype "passive"))
      (node (ref "C263") (pin "1") (pinfunction "1_1") (pintype "passive"))
      (node (ref "E5") (pin "2") (pinfunction "K_2") (pintype "passive"))
      (node (ref "E6") (pin "2") (pinfunction "K_2") (pintype "passive"))
      (node (ref "R123") (pin "1") (pinfunction "1_1") (pintype "passive"))
      (node (ref "R124") (pin "1") (pinfunction "1_1") (pintype "passive"))
      (node (ref "R138") (pin "1") (pinfunction "1_1") (pintype "passive"))
      (node (ref "V3") (pin "7") (pinfunction "0V_7") (pintype "passive"))
      (node (ref "V6") (pin "11") (pinfunction "GND_11") (pintype "power_in"))
      (node (ref "V6") (pin "12") (pinfunction "GND_12") (pintype "power_in"))
      (node (ref "V6") (pin "13") (pinfunction "GND_13") (pintype "power_in"))
      (node (ref "V6") (pin "18") (pinfunction "GND_18") (pintype "power_in"))
      (node (ref "V6") (pin "19") (pinfunction "GND_19") (pintype "power_in"))
      (node (ref "V6") (pin "24") (pinfunction "GND_24") (pintype "power_in"))
      (node (ref "V6") (pin "25") (pinfunction "GND_25") (pintype "power_in"))
      (node (ref "V6") (pin "26") (pinfunction "GND_26") (pintype "power_in"))
      (node (ref "V6") (pin "29") (pinfunction "GND_29") (pintype "power_in"))
      (node (ref "V6") (pin "3") (pinfunction "GND_3") (pintype "power_in"))
      (node (ref "V6") (pin "4") (pinfunction "GND_4") (pintype "power_in"))
      (node (ref "V6") (pin "5") (pinfunction "GND_5") (pintype "power_in"))
      (node (ref "V6") (pin "6") (pinfunction "GND_6") (pintype "power_in"))
      (node (ref "V8") (pin "A1") (pinfunction "VOUT+_A1") (pintype "output"))
      (node (ref "V8") (pin "A2") (pinfunction "VOUT+_A2") (pintype "output"))
      (node (ref "V8") (pin "B1") (pinfunction "VOUT+_B1") (pintype "output"))
      (node (ref "V8") (pin "B2") (pinfunction "VOUT+_B2") (pintype "output"))
      (node (ref "V8") (pin "B3") (pinfunction "GND_B3") (pintype "power_in"))
      (node (ref "V8") (pin "C1") (pinfunction "GND_C1") (pintype "power_in"))
      (node (ref "V8") (pin "C2") (pinfunction "GND_C2") (pintype "power_in"))
      (node (ref "V8") (pin "C3") (pinfunction "GND_C3") (pintype "power_in"))
      (node (ref "V8") (pin "C4") (pinfunction "GND_C4") (pintype "power_in"))
      (node (ref "V8") (pin "C5") (pinfunction "GND_C5") (pintype "power_in"))
      (node (ref "V8") (pin "D1") (pinfunction "GND_D1") (pintype "power_in"))
      (node (ref "V8") (pin "D2") (pinfunction "GND_D2") (pintype "power_in"))
      (node (ref "V8") (pin "D3") (pinfunction "GND_D3") (pintype "power_in"))
      (node (ref "V8") (pin "D4") (pinfunction "GND_D4") (pintype "power_in"))
      (node (ref "V8") (pin "D5") (pinfunction "GND_D5") (pintype "power_in"))
      (node (ref "V8") (pin "E1") (pinfunction "SYNC_E1") (pintype "power_in"))
      (node (ref "V8") (pin "E2") (pinfunction "GND_E2") (pintype "power_in"))
      (node (ref "V8") (pin "E3") (pinfunction "GND_E3") (pintype "power_in"))
      (node (ref "V8") (pin "E4") (pinfunction "GND_E4") (pintype "power_in"))
      (node (ref "V8") (pin "E5") (pinfunction "GND_E5") (pintype "power_in"))
      (node (ref "V8") (pin "F2") (pinfunction "GND_F2") (pintype "power_in"))
      (node (ref "V8") (pin "F3") (pinfunction "GND_F3") (pintype "power_in"))
      (node (ref "V8") (pin "F4") (pinfunction "GND_F4") (pintype "power_in"))
      (node (ref "V8") (pin "F5") (pinfunction "GND_F5") (pintype "power_in"))
      (node (ref "V8") (pin "G2") (pinfunction "GND_G2") (pintype "power_in"))
      (node (ref "V8") (pin "H1") (pinfunction "GND_H1") (pintype "power_in"))
      (node (ref "V8") (pin "H2") (pinfunction "GND_H2") (pintype "power_in"))
      (node (ref "V8") (pin "H3") (pinfunction "GND_H3") (pintype "power_in"))
    )
    (net (code "16") (name "GND") (class "Default")
      (node (ref "C198") (pin "2") (pinfunction "2_2") (pintype "passive"))
      (node (ref "C199") (pin "2") (pinfunction "2_2") (pintype "passive"))
      (node (ref "C202") (pin "2") (pinfunction "2_2") (pintype "passive"))
      (node (ref "C203") (pin "2") (pinfunction "2_2") (pintype "passive"))
      (node (ref "C217") (pin "1") (pinfunction "1_1") (pintype "passive"))
      (node (ref "C219") (pin "1") (pinfunction "1_1") (pintype "passive"))
      (node (ref "C220") (pin "1") (pinfunction "1_1") (pintype "passive"))
      (node (ref "C261") (pin "1") (pinfunction "1_1") (pintype "passive"))
      (node (ref "DC_IN") (pin "2") (pinfunction "2_2") (pintype "passive"))
      (node (ref "E10") (pin "2") (pinfunction "K_2") (pintype "passive"))
      (node (ref "E3") (pin "2") (pinfunction "K_2") (pintype "passive"))
      (node (ref "E4") (pin "2") (pinfunction "K_2") (pintype "passive"))
      (node (ref "E7") (pin "2") (pinfunction "K_2") (pintype "passive"))
      (node (ref "E8") (pin "2") (pinfunction "K_2") (pintype "passive"))
      (node (ref "LED2") (pin "2") (pinfunction "K_2") (pintype "passive"))
      (node (ref "R114") (pin "1") (pinfunction "1_1") (pintype "passive"))
      (node (ref "R115") (pin "1") (pinfunction "1_1") (pintype "passive"))
      (node (ref "R130") (pin "1") (pinfunction "1_1") (pintype "passive"))
      (node (ref "V1") (pin "1") (pinfunction "GND_1") (pintype "passive"))
      (node (ref "V2") (pin "13") (pinfunction "EPAD_13") (pintype "passive"))
      (node (ref "V2") (pin "4") (pinfunction "GND_4") (pintype "power_in"))
      (node (ref "V3") (pin "1") (pinfunction "GND_1") (pintype "passive"))
      (node (ref "V7") (pin "3") (pinfunction "GND_3") (pintype "power_in"))
    )
    (net (code "17") (name "Net-(C204-Pad1)") (class "Default")
      (node (ref "C204") (pin "1") (pinfunction "1_1") (pintype "passive"))
      (node (ref "R122") (pin "1") (pinfunction "1_1") (pintype "passive"))
      (node (ref "R128") (pin "1") (pinfunction "1_1") (pintype "passive"))
      (node (ref "R130") (pin "2") (pinfunction "2_2") (pintype "passive"))
    )
    (net (code "18") (name "Net-(C218-Pad1)") (class "Default")
      (node (ref "C218") (pin "1") (pinfunction "1_1") (pintype "passive"))
      (node (ref "R129") (pin "1") (pinfunction "1_1") (pintype "passive"))
    )
    (net (code "19") (name "Net-(E2-A)") (class "Default")
      (node (ref "E2") (pin "1") (pinfunction "A_1") (pintype "passive"))
      (node (ref "V1") (pin "8") (pinfunction "CS_8") (pintype "passive"))
    )
    (net (code "20") (name "Net-(E6-A)") (class "Default")
      (node (ref "E6") (pin "1") (pinfunction "A_1") (pintype "passive"))
      (node (ref "V3") (pin "8") (pinfunction "CS_8") (pintype "passive"))
    )
    (net (code "21") (name "Net-(LED2-A)") (class "Default")
      (node (ref "LED2") (pin "1") (pinfunction "A_1") (pintype "passive"))
      (node (ref "R163") (pin "2") (pinfunction "2_2") (pintype "passive"))
    )
    (net (code "22") (name "Net-(V2-ADJ1)") (class "Default")
      (node (ref "R113") (pin "1") (pinfunction "1_1") (pintype "passive"))
      (node (ref "R114") (pin "2") (pinfunction "2_2") (pintype "passive"))
      (node (ref "V2") (pin "12") (pinfunction "ADJ1_12") (pintype "input"))
    )
    (net (code "23") (name "Net-(V2-ADJ2)") (class "Default")
      (node (ref "R112") (pin "1") (pinfunction "1_1") (pintype "passive"))
      (node (ref "R115") (pin "2") (pinfunction "2_2") (pintype "passive"))
      (node (ref "V2") (pin "7") (pinfunction "ADJ2_7") (pintype "input"))
    )
    (net (code "24") (name "Net-(V2-BYP1)") (class "Default")
      (node (ref "C200") (pin "1") (pinfunction "1_1") (pintype "passive"))
      (node (ref "V2") (pin "1") (pinfunction "BYP1_1") (pintype "passive"))
    )
    (net (code "25") (name "Net-(V2-BYP2)") (class "Default")
      (node (ref "C201") (pin "1") (pinfunction "1_1") (pintype "passive"))
      (node (ref "V2") (pin "6") (pinfunction "BYP2_6") (pintype "passive"))
    )
    (net (code "26") (name "Net-(V4-ADJ1)") (class "Default")
      (node (ref "R117") (pin "1") (pinfunction "1_1") (pintype "passive"))
      (node (ref "R120") (pin "2") (pinfunction "2_2") (pintype "passive"))
      (node (ref "V4") (pin "12") (pinfunction "ADJ1_12") (pintype "input"))
    )
    (net (code "27") (name "Net-(V4-ADJ2)") (class "Default")
      (node (ref "R116") (pin "1") (pinfunction "1_1") (pintype "passive"))
      (node (ref "R121") (pin "2") (pinfunction "2_2") (pintype "passive"))
      (node (ref "V4") (pin "7") (pinfunction "ADJ2_7") (pintype "input"))
    )
    (net (code "28") (name "Net-(V4-BYP1)") (class "Default")
      (node (ref "C207") (pin "1") (pinfunction "1_1") (pintype "passive"))
      (node (ref "V4") (pin "1") (pinfunction "BYP1_1") (pintype "passive"))
    )
    (net (code "29") (name "Net-(V4-BYP2)") (class "Default")
      (node (ref "C208") (pin "1") (pinfunction "1_1") (pintype "passive"))
      (node (ref "V4") (pin "6") (pinfunction "BYP2_6") (pintype "passive"))
    )
    (net (code "30") (name "Net-(V5-C1+)") (class "Default")
      (node (ref "C223") (pin "2") (pinfunction "2_2") (pintype "passive"))
      (node (ref "V5") (pin "10") (pinfunction "C1+_10") (pintype "passive"))
    )
    (net (code "31") (name "Net-(V5-C1-)") (class "Default")
      (node (ref "C223") (pin "1") (pinfunction "1_1") (pintype "passive"))
      (node (ref "V5") (pin "9") (pinfunction "C1-_9") (pintype "passive"))
    )
    (net (code "32") (name "Net-(V5-CPOUT)") (class "Default")
      (node (ref "C221") (pin "1") (pinfunction "1_1") (pintype "passive"))
      (node (ref "V5") (pin "5") (pinfunction "CPOUT_5") (pintype "power_in"))
    )
    (net (code "33") (name "Net-(V5-EN+)") (class "Default")
      (node (ref "R132") (pin "1") (pinfunction "1_1") (pintype "passive"))
      (node (ref "V5") (pin "12") (pinfunction "EN+_12") (pintype "input"))
      (node (ref "V5") (pin "8") (pinfunction "EN-_8") (pintype "input"))
    )
    (net (code "34") (name "Net-(V5-FB+)") (class "Default")
      (node (ref "R131") (pin "1") (pinfunction "1_1") (pintype "passive"))
      (node (ref "R134") (pin "2") (pinfunction "2_2") (pintype "passive"))
      (node (ref "V5") (pin "2") (pinfunction "FB+_2") (pintype "input"))
    )
    (net (code "35") (name "Net-(V5-FB-)") (class "Default")
      (node (ref "R135") (pin "1") (pinfunction "1_1") (pintype "passive"))
      (node (ref "R136") (pin "2") (pinfunction "2_2") (pintype "passive"))
      (node (ref "V5") (pin "7") (pinfunction "FB-_7") (pintype "input"))
    )
    (net (code "36") (name "Net-(V5-PGOOD)") (class "Default")
      (node (ref "R133") (pin "1") (pinfunction "1_1") (pintype "passive"))
      (node (ref "V5") (pin "1") (pinfunction "PGOOD_1") (pintype "open_collector"))
    )
    (net (code "37") (name "Net-(V6A-ADJ1)") (class "Default")
      (node (ref "R119") (pin "1") (pinfunction "1_1") (pintype "passive"))
      (node (ref "R123") (pin "2") (pinfunction "2_2") (pintype "passive"))
      (node (ref "V6") (pin "27") (pinfunction "ADJ1_27") (pintype "input"))
    )
    (net (code "38") (name "Net-(V6A-ADJ2)") (class "Default")
      (node (ref "R118") (pin "1") (pinfunction "1_1") (pintype "passive"))
      (node (ref "R124") (pin "2") (pinfunction "2_2") (pintype "passive"))
      (node (ref "V6") (pin "10") (pinfunction "ADJ2_10") (pintype "input"))
    )
    (net (code "39") (name "Net-(V6A-BYP1)") (class "Default")
      (node (ref "C211") (pin "1") (pinfunction "1_1") (pintype "passive"))
      (node (ref "V6") (pin "28") (pinfunction "BYP1_28") (pintype "passive"))
    )
    (net (code "40") (name "Net-(V6A-BYP2)") (class "Default")
      (node (ref "C212") (pin "1") (pinfunction "1_1") (pintype "passive"))
      (node (ref "V6") (pin "9") (pinfunction "BYP2_9") (pintype "passive"))
    )
    (net (code "41") (name "Net-(V6A-PWRGD1)") (class "Default")
      (node (ref "R127") (pin "1") (pinfunction "1_1") (pintype "passive"))
      (node (ref "V6") (pin "22") (pinfunction "PWRGD1_22") (pintype "power_in"))
    )
    (net (code "42") (name "Net-(V6A-PWRGD2)") (class "Default")
      (node (ref "R126") (pin "1") (pinfunction "1_1") (pintype "passive"))
      (node (ref "V6") (pin "15") (pinfunction "PWRGD2_15") (pintype "power_in"))
    )
    (net (code "43") (name "Net-(V7-BST)") (class "Default")
      (node (ref "R129") (pin "2") (pinfunction "2_2") (pintype "passive"))
      (node (ref "V7") (pin "4") (pinfunction "BST_4") (pintype "power_in"))
    )
    (net (code "44") (name "Net-(V7-EN)") (class "Default")
      (node (ref "R125") (pin "2") (pinfunction "2_2") (pintype "passive"))
      (node (ref "V7") (pin "5") (pinfunction "EN_5") (pintype "passive"))
    )
    (net (code "45") (name "Net-(V7-FB)") (class "Default")
      (node (ref "R128") (pin "2") (pinfunction "2_2") (pintype "passive"))
      (node (ref "V7") (pin "6") (pinfunction "FB_6") (pintype "passive"))
    )
    (net (code "46") (name "Net-(V7-SW)") (class "Default")
      (node (ref "C218") (pin "2") (pinfunction "2_2") (pintype "passive"))
      (node (ref "L4") (pin "1") (pinfunction "1_1") (pintype "passive"))
      (node (ref "V7") (pin "2") (pinfunction "SW_2") (pintype "output"))
    )
    (net (code "47") (name "Net-(V8A-FB)") (class "Default")
      (node (ref "R137") (pin "2") (pinfunction "2_2") (pintype "passive"))
      (node (ref "V8") (pin "A3") (pinfunction "FB_A3") (pintype "passive"))
    )
    (net (code "48") (name "Net-(V8A-RT)") (class "Default")
      (node (ref "R138") (pin "2") (pinfunction "2_2") (pintype "passive"))
      (node (ref "V8") (pin "G1") (pinfunction "RT_G1") (pintype "passive"))
    )
    (net (code "49") (name "Net-(V8A-SS)") (class "Default")
      (node (ref "C230") (pin "1") (pinfunction "1_1") (pintype "passive"))
      (node (ref "V8") (pin "F1") (pinfunction "SS_F1") (pintype "passive"))
    )
    (net (code "50") (name "unconnected-(V1-Ctrl-Pad3)") (class "Default")
      (node (ref "V1") (pin "3") (pinfunction "Ctrl_3") (pintype "passive+no_connect"))
    )
    (net (code "51") (name "unconnected-(V1-NC-Pad5)") (class "Default")
      (node (ref "V1") (pin "5") (pinfunction "NC_5") (pintype "passive+no_connect"))
    )
    (net (code "52") (name "unconnected-(V3-Ctrl-Pad3)") (class "Default")
      (node (ref "V3") (pin "3") (pinfunction "Ctrl_3") (pintype "passive+no_connect"))
    )
    (net (code "53") (name "unconnected-(V3-NC-Pad5)") (class "Default")
      (node (ref "V3") (pin "5") (pinfunction "NC_5") (pintype "passive+no_connect"))
    )
  )
)
